# arduino_Uno_Rev3-02-TH.net
KiCad netlist of a schematic drawn in EAGLE
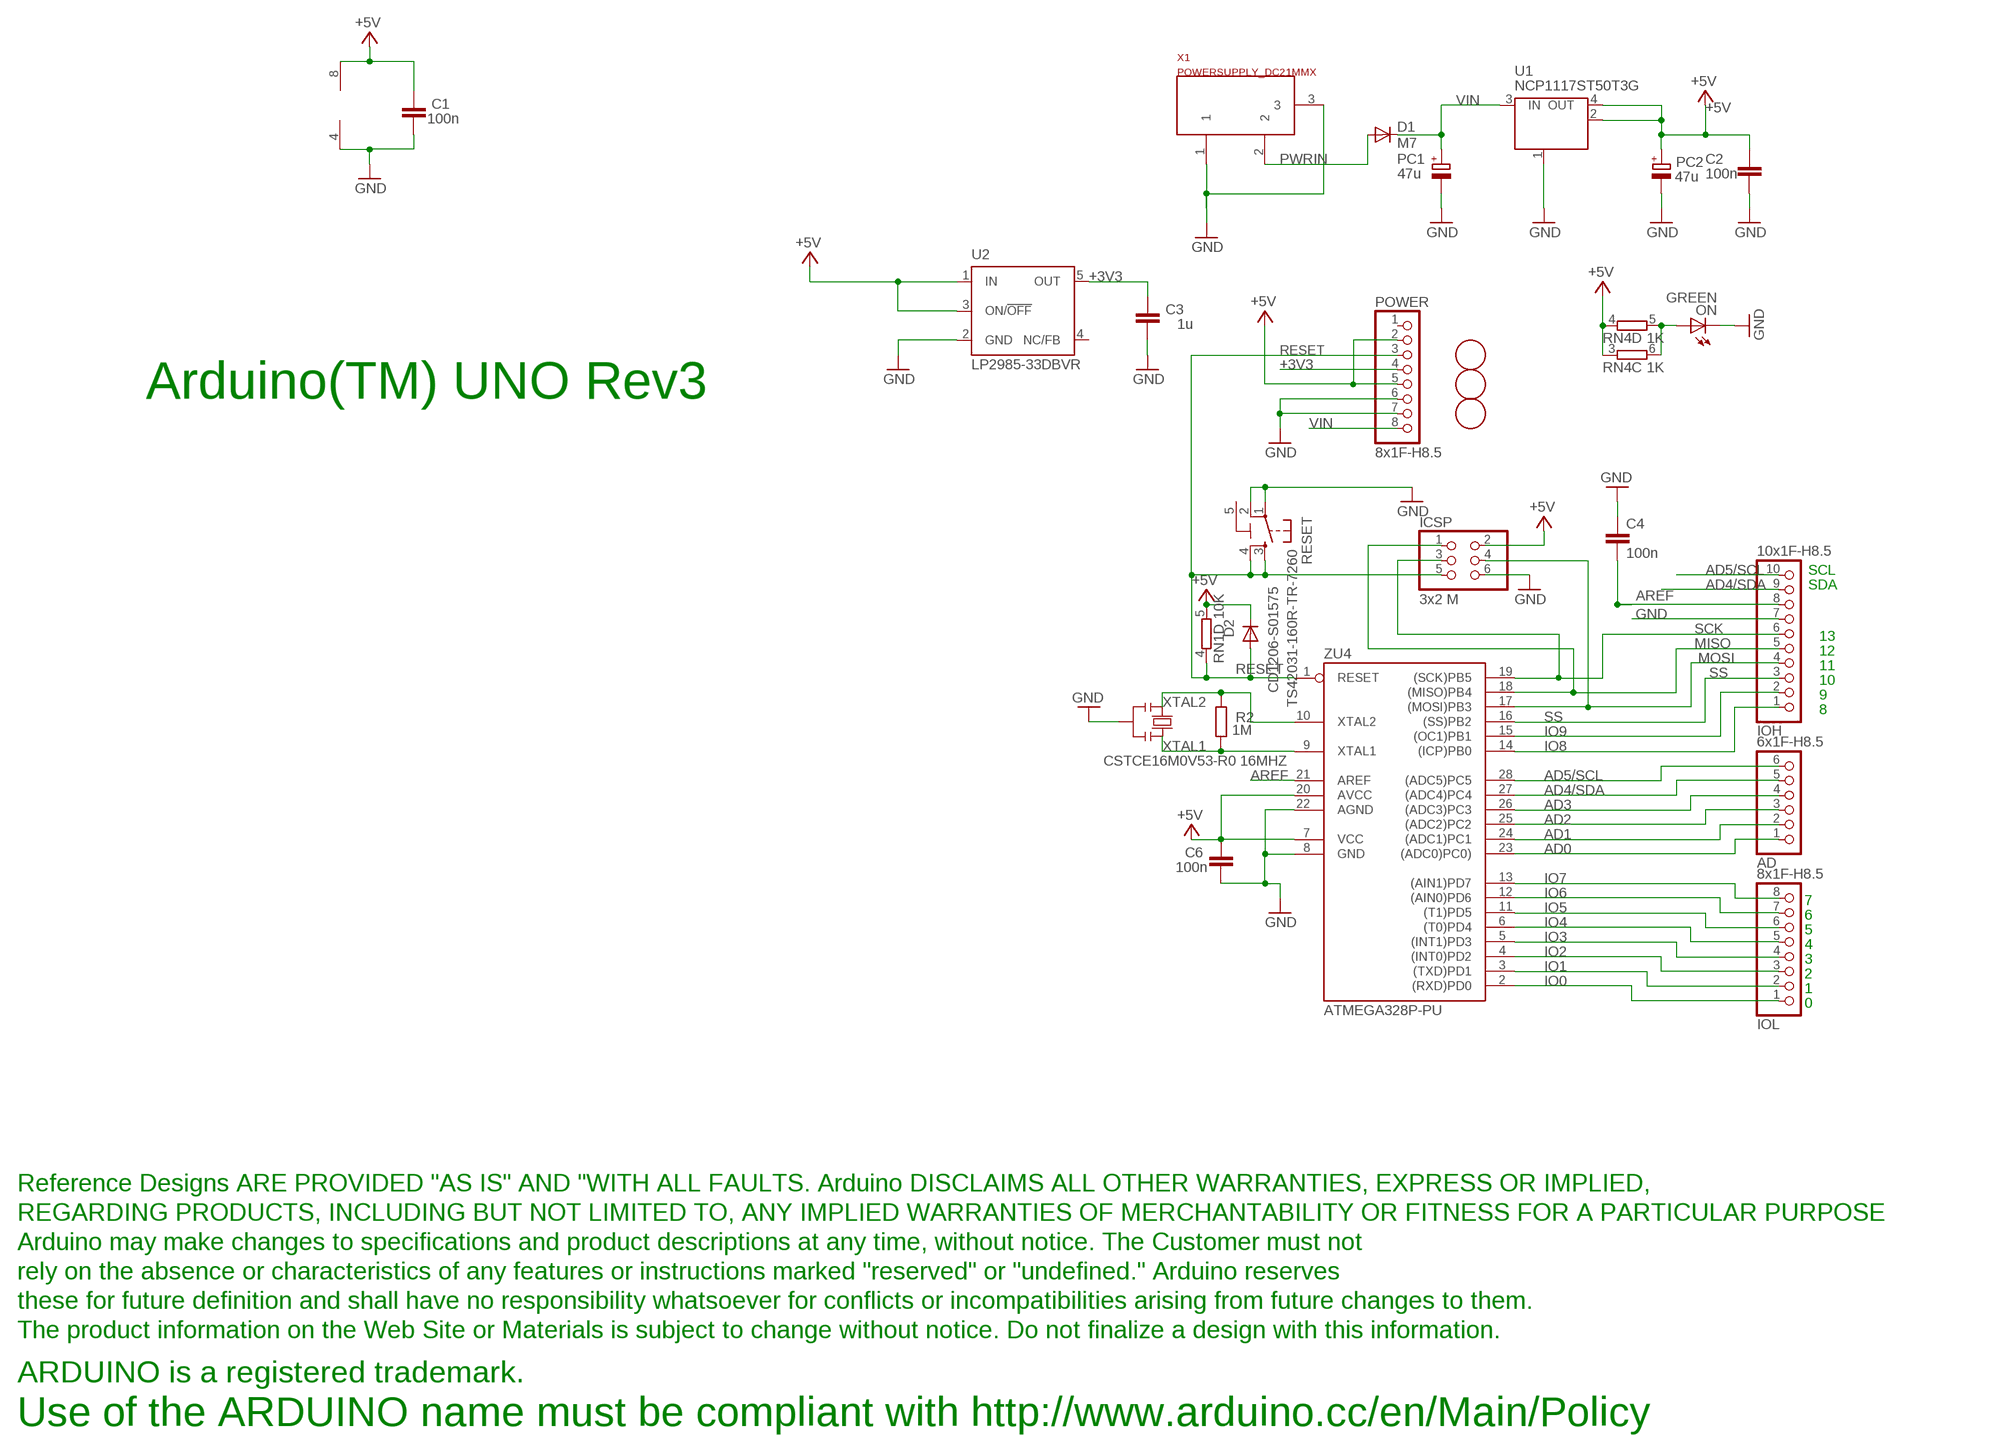
[diagram p0: schematic, sheet 1]

(export (version "E")
  (design (tool "Eeschema 10.0.6"))
  (components
    (comp (ref "AD")
      (value "6x1F-H8.5")
      (footprint "eagle-import:1X06")
      (libsource (lib "eagle-import") (part "PINHD-1X6"))
    )
    (comp (ref "C1")
      (value "100n")
      (footprint "eagle-import:C0603-ROUND")
      (libsource (lib "eagle-import") (part "C-EU0603-RND"))
    )
    (comp (ref "C2")
      (value "100n")
      (footprint "eagle-import:C0603-ROUND")
      (libsource (lib "eagle-import") (part "C-EU0603-RND"))
    )
    (comp (ref "C3")
      (value "1u")
      (footprint "eagle-import:C0603-ROUND")
      (libsource (lib "eagle-import") (part "C-EU0603-RND"))
    )
    (comp (ref "C4")
      (value "100n")
      (footprint "eagle-import:C0603-ROUND")
      (libsource (lib "eagle-import") (part "C-EU0603-RND"))
    )
    (comp (ref "C6")
      (value "100n")
      (footprint "eagle-import:C0603-ROUND")
      (libsource (lib "eagle-import") (part "C-EU0603-RND"))
    )
    (comp (ref "D1")
      (value "M7")
      (footprint "eagle-import:SMB")
      (libsource (lib "eagle-import") (part "DIODE-SMB"))
    )
    (comp (ref "D2")
      (value "CD1206-S01575")
      (footprint "eagle-import:MINIMELF")
      (libsource (lib "eagle-import") (part "DIODE-MINIMELF"))
    )
    (comp (ref "FD1")
      (value "FIDUCIALMOUNT")
      (footprint "eagle-import:FIDUCIA-MOUNT")
      (libsource (lib "eagle-import") (part "FIDUCIALMOUNT"))
    )
    (comp (ref "FD2")
      (value "FIDUCIALMOUNT")
      (footprint "eagle-import:FIDUCIA-MOUNT")
      (libsource (lib "eagle-import") (part "FIDUCIALMOUNT"))
    )
    (comp (ref "FD3")
      (value "FIDUCIALMOUNT")
      (footprint "eagle-import:FIDUCIA-MOUNT")
      (libsource (lib "eagle-import") (part "FIDUCIALMOUNT"))
    )
    (comp (ref "ICSP")
      (value "3x2 M")
      (footprint "eagle-import:2X03")
      (libsource (lib "eagle-import") (part "PINHD-2X3"))
    )
    (comp (ref "IOH")
      (value "10x1F-H8.5")
      (footprint "eagle-import:1X10")
      (libsource (lib "eagle-import") (part "PINHD-1X10_ARD"))
    )
    (comp (ref "IOL")
      (value "8x1F-H8.5")
      (footprint "eagle-import:1X08")
      (libsource (lib "eagle-import") (part "PINHD-1X8"))
    )
    (comp (ref "ON")
      (value "GREEN")
      (footprint "eagle-import:CHIP-LED0805")
      (libsource (lib "eagle-import") (part "LEDCHIP-LED0805"))
    )
    (comp (ref "PC1")
      (value "47u")
      (footprint "eagle-import:PANASONIC_D")
      (libsource (lib "eagle-import") (part "CPOL-EUD"))
    )
    (comp (ref "PC2")
      (value "47u")
      (footprint "eagle-import:PANASONIC_D")
      (libsource (lib "eagle-import") (part "CPOL-EUD"))
    )
    (comp (ref "POWER")
      (value "8x1F-H8.5")
      (footprint "eagle-import:1X08")
      (libsource (lib "eagle-import") (part "PINHD-1X8"))
    )
    (comp (ref "R2")
      (value "1M")
      (footprint "eagle-import:R0603-ROUND")
      (libsource (lib "eagle-import") (part "R-EU_R0603"))
    )
    (comp (ref "RESET")
      (value "TS42031-160R-TR-7260")
      (footprint "eagle-import:TS42")
      (libsource (lib "eagle-import") (part "TS42"))
    )
    (comp (ref "RN1")
      (value "10K")
      (footprint "eagle-import:CAY16")
      (libsource (lib "eagle-import") (part "4R-NCAY16"))
    )
    (comp (ref "RN4")
      (value "1K")
      (footprint "eagle-import:CAY16")
      (libsource (lib "eagle-import") (part "4R-NCAY16"))
    )
    (comp (ref "U$1")
      (value "DISCLAIMER")
      (footprint "eagle-import:DISCLAIMER")
      (libsource (lib "eagle-import") (part "DISCLAIMER"))
    )
    (comp (ref "U1")
      (value "NCP1117ST50T3G")
      (footprint "eagle-import:SOT223")
      (libsource (lib "eagle-import") (part "MC33269ST-3.3T3"))
    )
    (comp (ref "U2")
      (value "LP2985-33DBVR")
      (footprint "eagle-import:SOT23-DBV")
      (libsource (lib "eagle-import") (part "LP2985-XXDBVR33"))
    )
    (comp (ref "U5")
      (value "LMV358IDGKR")
      (footprint "eagle-import:MSOP08")
      (libsource (lib "eagle-import") (part "LMV358?MMX"))
    )
    (comp (ref "X1")
      (value "POWERSUPPLY_DC21MMX")
      (footprint "eagle-import:POWERSUPPLY_DC-21MM")
      (libsource (lib "eagle-import") (part "POWERSUPPLY_DC21MMX"))
    )
    (comp (ref "Y2")
      (value "CSTCE16M0V53-R0 16MHZ")
      (footprint "eagle-import:RESONATOR")
      (libsource (lib "eagle-import") (part "RESONATORMU"))
    )
    (comp (ref "ZU4")
      (value "ATMEGA328P-PU")
      (footprint "eagle-import:DIL28-3")
      (libsource (lib "eagle-import") (part "ATMEGA328P-PU"))
    )
  )
  (nets
    (net (code "1") (name "+5V") (class "Default")
      (node (ref "C1") (pin "2") (pinfunction "2_2") (pintype "passive"))
      (node (ref "C2") (pin "2") (pinfunction "2_2") (pintype "passive"))
      (node (ref "C6") (pin "2") (pinfunction "2_2") (pintype "passive"))
      (node (ref "D2") (pin "C") (pinfunction "C_C") (pintype "passive"))
      (node (ref "ICSP") (pin "2") (pinfunction "2_2") (pintype "passive"))
      (node (ref "PC2") (pin "+") (pinfunction "+_+") (pintype "passive"))
      (node (ref "POWER") (pin "2") (pinfunction "2_2") (pintype "passive"))
      (node (ref "POWER") (pin "5") (pinfunction "5_5") (pintype "passive"))
      (node (ref "RN1") (pin "5") (pinfunction "2_5") (pintype "passive"))
      (node (ref "RN4") (pin "3") (pinfunction "1_3") (pintype "passive"))
      (node (ref "RN4") (pin "4") (pinfunction "1_4") (pintype "passive"))
      (node (ref "U1") (pin "2") (pinfunction "OUT_2") (pintype "passive"))
      (node (ref "U1") (pin "4") (pinfunction "OUT_4") (pintype "passive"))
      (node (ref "U2") (pin "1") (pinfunction "IN_1") (pintype "input"))
      (node (ref "U2") (pin "3") (pinfunction "ON/~{OFF}_3") (pintype "input"))
      (node (ref "U5") (pin "8") (pinfunction "V+_8") (pintype "power_in"))
      (node (ref "ZU4") (pin "20") (pinfunction "AVCC_20") (pintype "power_in"))
      (node (ref "ZU4") (pin "7") (pinfunction "VCC_7") (pintype "power_in"))
    )
    (net (code "2") (name "/+3V3") (class "Default")
      (node (ref "C3") (pin "2") (pinfunction "2_2") (pintype "passive"))
      (node (ref "POWER") (pin "4") (pinfunction "4_4") (pintype "passive"))
      (node (ref "U2") (pin "5") (pinfunction "OUT_5") (pintype "passive"))
    )
    (net (code "3") (name "/5-GND") (class "Default")
      (node (ref "RESET") (pin "5") (pinfunction "5-GND_5") (pintype "power_in"))
    )
    (net (code "4") (name "/AD0") (class "Default")
      (node (ref "AD") (pin "1") (pinfunction "1_1") (pintype "passive"))
      (node (ref "ZU4") (pin "23") (pinfunction "(ADC0)PC0)_23") (pintype "bidirectional"))
    )
    (net (code "5") (name "/AD1") (class "Default")
      (node (ref "AD") (pin "2") (pinfunction "2_2") (pintype "passive"))
      (node (ref "ZU4") (pin "24") (pinfunction "(ADC1)PC1_24") (pintype "bidirectional"))
    )
    (net (code "6") (name "/AD2") (class "Default")
      (node (ref "AD") (pin "3") (pinfunction "3_3") (pintype "passive"))
      (node (ref "ZU4") (pin "25") (pinfunction "(ADC2)PC2_25") (pintype "bidirectional"))
    )
    (net (code "7") (name "/AD3") (class "Default")
      (node (ref "AD") (pin "4") (pinfunction "4_4") (pintype "passive"))
      (node (ref "ZU4") (pin "26") (pinfunction "(ADC3)PC3_26") (pintype "bidirectional"))
    )
    (net (code "8") (name "/AD4{slash}SDA") (class "Default")
      (node (ref "AD") (pin "5") (pinfunction "5_5") (pintype "passive"))
      (node (ref "IOH") (pin "9") (pinfunction "9_9") (pintype "passive"))
      (node (ref "ZU4") (pin "27") (pinfunction "(ADC4)PC4_27") (pintype "bidirectional"))
    )
    (net (code "9") (name "/AD5{slash}SCL") (class "Default")
      (node (ref "AD") (pin "6") (pinfunction "6_6") (pintype "passive"))
      (node (ref "IOH") (pin "10") (pinfunction "10_10") (pintype "passive"))
      (node (ref "ZU4") (pin "28") (pinfunction "(ADC5)PC5_28") (pintype "bidirectional"))
    )
    (net (code "10") (name "/AREF") (class "Default")
      (node (ref "C4") (pin "2") (pinfunction "2_2") (pintype "passive"))
      (node (ref "IOH") (pin "8") (pinfunction "8_8") (pintype "passive"))
      (node (ref "ZU4") (pin "21") (pinfunction "AREF_21") (pintype "passive"))
    )
    (net (code "11") (name "/IO0") (class "Default")
      (node (ref "IOL") (pin "1") (pinfunction "1_1") (pintype "passive"))
      (node (ref "ZU4") (pin "2") (pinfunction "(RXD)PD0_2") (pintype "bidirectional"))
    )
    (net (code "12") (name "/IO1") (class "Default")
      (node (ref "IOL") (pin "2") (pinfunction "2_2") (pintype "passive"))
      (node (ref "ZU4") (pin "3") (pinfunction "(TXD)PD1_3") (pintype "bidirectional"))
    )
    (net (code "13") (name "/IO2") (class "Default")
      (node (ref "IOL") (pin "3") (pinfunction "3_3") (pintype "passive"))
      (node (ref "ZU4") (pin "4") (pinfunction "(INT0)PD2_4") (pintype "bidirectional"))
    )
    (net (code "14") (name "/IO3") (class "Default")
      (node (ref "IOL") (pin "4") (pinfunction "4_4") (pintype "passive"))
      (node (ref "ZU4") (pin "5") (pinfunction "(INT1)PD3_5") (pintype "bidirectional"))
    )
    (net (code "15") (name "/IO4") (class "Default")
      (node (ref "IOL") (pin "5") (pinfunction "5_5") (pintype "passive"))
      (node (ref "ZU4") (pin "6") (pinfunction "(T0)PD4_6") (pintype "bidirectional"))
    )
    (net (code "16") (name "/IO5") (class "Default")
      (node (ref "IOL") (pin "6") (pinfunction "6_6") (pintype "passive"))
      (node (ref "ZU4") (pin "11") (pinfunction "(T1)PD5_11") (pintype "bidirectional"))
    )
    (net (code "17") (name "/IO6") (class "Default")
      (node (ref "IOL") (pin "7") (pinfunction "7_7") (pintype "passive"))
      (node (ref "ZU4") (pin "12") (pinfunction "(AIN0)PD6_12") (pintype "bidirectional"))
    )
    (net (code "18") (name "/IO7") (class "Default")
      (node (ref "IOL") (pin "8") (pinfunction "8_8") (pintype "passive"))
      (node (ref "ZU4") (pin "13") (pinfunction "(AIN1)PD7_13") (pintype "bidirectional"))
    )
    (net (code "19") (name "/IO8") (class "Default")
      (node (ref "IOH") (pin "1") (pinfunction "1_1") (pintype "passive"))
      (node (ref "ZU4") (pin "14") (pinfunction "(ICP)PB0_14") (pintype "bidirectional"))
    )
    (net (code "20") (name "/IO9") (class "Default")
      (node (ref "IOH") (pin "2") (pinfunction "2_2") (pintype "passive"))
      (node (ref "ZU4") (pin "15") (pinfunction "(OC1)PB1_15") (pintype "bidirectional"))
    )
    (net (code "21") (name "/MISO") (class "Default")
      (node (ref "ICSP") (pin "1") (pinfunction "1_1") (pintype "passive"))
      (node (ref "IOH") (pin "5") (pinfunction "5_5") (pintype "passive"))
      (node (ref "ZU4") (pin "18") (pinfunction "(MISO)PB4_18") (pintype "bidirectional"))
    )
    (net (code "22") (name "/MOSI") (class "Default")
      (node (ref "ICSP") (pin "4") (pinfunction "4_4") (pintype "passive"))
      (node (ref "IOH") (pin "4") (pinfunction "4_4") (pintype "passive"))
      (node (ref "ZU4") (pin "17") (pinfunction "(MOSI)PB3_17") (pintype "bidirectional"))
    )
    (net (code "23") (name "/PWRIN") (class "Default")
      (node (ref "D1") (pin "A") (pinfunction "A_A") (pintype "passive"))
      (node (ref "X1") (pin "2") (pinfunction "2_2") (pintype "power_in"))
    )
    (net (code "24") (name "/RESET") (class "Default")
      (node (ref "D2") (pin "A") (pinfunction "A_A") (pintype "passive"))
      (node (ref "ICSP") (pin "5") (pinfunction "5_5") (pintype "passive"))
      (node (ref "POWER") (pin "3") (pinfunction "3_3") (pintype "passive"))
      (node (ref "RESET") (pin "3") (pinfunction "3_3") (pintype "passive"))
      (node (ref "RESET") (pin "4") (pinfunction "4_4") (pintype "passive"))
      (node (ref "RN1") (pin "4") (pinfunction "1_4") (pintype "passive"))
      (node (ref "ZU4") (pin "1") (pinfunction "RESET_1") (pintype "input"))
    )
    (net (code "25") (name "/SCK") (class "Default")
      (node (ref "ICSP") (pin "3") (pinfunction "3_3") (pintype "passive"))
      (node (ref "IOH") (pin "6") (pinfunction "6_6") (pintype "passive"))
      (node (ref "ZU4") (pin "19") (pinfunction "(SCK)PB5_19") (pintype "bidirectional"))
    )
    (net (code "26") (name "/SS") (class "Default")
      (node (ref "IOH") (pin "3") (pinfunction "3_3") (pintype "passive"))
      (node (ref "ZU4") (pin "16") (pinfunction "(SS)PB2_16") (pintype "bidirectional"))
    )
    (net (code "27") (name "/VIN") (class "Default")
      (node (ref "D1") (pin "C") (pinfunction "C_C") (pintype "passive"))
      (node (ref "PC1") (pin "+") (pinfunction "+_+") (pintype "passive"))
      (node (ref "POWER") (pin "8") (pinfunction "8_8") (pintype "passive"))
      (node (ref "U1") (pin "3") (pinfunction "IN_3") (pintype "input"))
    )
    (net (code "28") (name "/XTAL1") (class "Default")
      (node (ref "R2") (pin "1") (pinfunction "1_1") (pintype "passive"))
      (node (ref "Y2") (pin "3") (pinfunction "3_3") (pintype "passive"))
      (node (ref "ZU4") (pin "9") (pinfunction "XTAL1_9") (pintype "bidirectional"))
    )
    (net (code "29") (name "/XTAL2") (class "Default")
      (node (ref "R2") (pin "2") (pinfunction "2_2") (pintype "passive"))
      (node (ref "Y2") (pin "1") (pinfunction "1_1") (pintype "passive"))
      (node (ref "ZU4") (pin "10") (pinfunction "XTAL2_10") (pintype "bidirectional"))
    )
    (net (code "30") (name "GND") (class "Default")
      (node (ref "C1") (pin "1") (pinfunction "1_1") (pintype "passive"))
      (node (ref "C2") (pin "1") (pinfunction "1_1") (pintype "passive"))
      (node (ref "C3") (pin "1") (pinfunction "1_1") (pintype "passive"))
      (node (ref "C4") (pin "1") (pinfunction "1_1") (pintype "passive"))
      (node (ref "C6") (pin "1") (pinfunction "1_1") (pintype "passive"))
      (node (ref "ICSP") (pin "6") (pinfunction "6_6") (pintype "passive"))
      (node (ref "IOH") (pin "7") (pinfunction "7_7") (pintype "passive"))
      (node (ref "ON") (pin "C") (pinfunction "C_C") (pintype "passive"))
      (node (ref "PC1") (pin "-") (pinfunction "-_-") (pintype "passive"))
      (node (ref "PC2") (pin "-") (pinfunction "-_-") (pintype "passive"))
      (node (ref "POWER") (pin "6") (pinfunction "6_6") (pintype "passive"))
      (node (ref "POWER") (pin "7") (pinfunction "7_7") (pintype "passive"))
      (node (ref "RESET") (pin "1") (pinfunction "1_1") (pintype "passive"))
      (node (ref "RESET") (pin "2") (pinfunction "2_2") (pintype "passive"))
      (node (ref "U1") (pin "1") (pinfunction "GND/ADJ_1") (pintype "input"))
      (node (ref "U2") (pin "2") (pinfunction "GND_2") (pintype "power_in"))
      (node (ref "U5") (pin "4") (pinfunction "V-_4") (pintype "power_in"))
      (node (ref "X1") (pin "1") (pinfunction "1_1") (pintype "power_in"))
      (node (ref "X1") (pin "3") (pinfunction "3_3") (pintype "power_in"))
      (node (ref "Y2") (pin "2") (pinfunction "2_2") (pintype "passive"))
      (node (ref "ZU4") (pin "22") (pinfunction "AGND_22") (pintype "power_in"))
      (node (ref "ZU4") (pin "8") (pinfunction "GND_8") (pintype "power_in"))
    )
    (net (code "31") (name "Net-(RN4C-2)") (class "Default")
      (node (ref "ON") (pin "A") (pinfunction "A_A") (pintype "passive"))
      (node (ref "RN4") (pin "5") (pinfunction "2_5") (pintype "passive"))
      (node (ref "RN4") (pin "6") (pinfunction "2_6") (pintype "passive"))
    )
    (net (code "32") (name "unconnected-(POWER-Pad1)") (class "Default")
      (node (ref "POWER") (pin "1") (pinfunction "1_1") (pintype "passive"))
    )
    (net (code "33") (name "unconnected-(U2-NC{slash}FB-Pad4)") (class "Default")
      (node (ref "U2") (pin "4") (pinfunction "NC/FB_4") (pintype "passive"))
    )
  )
)
